# TJMakes_OLED.net
KiCad netlist of a schematic drawn in EasyEDA Pro
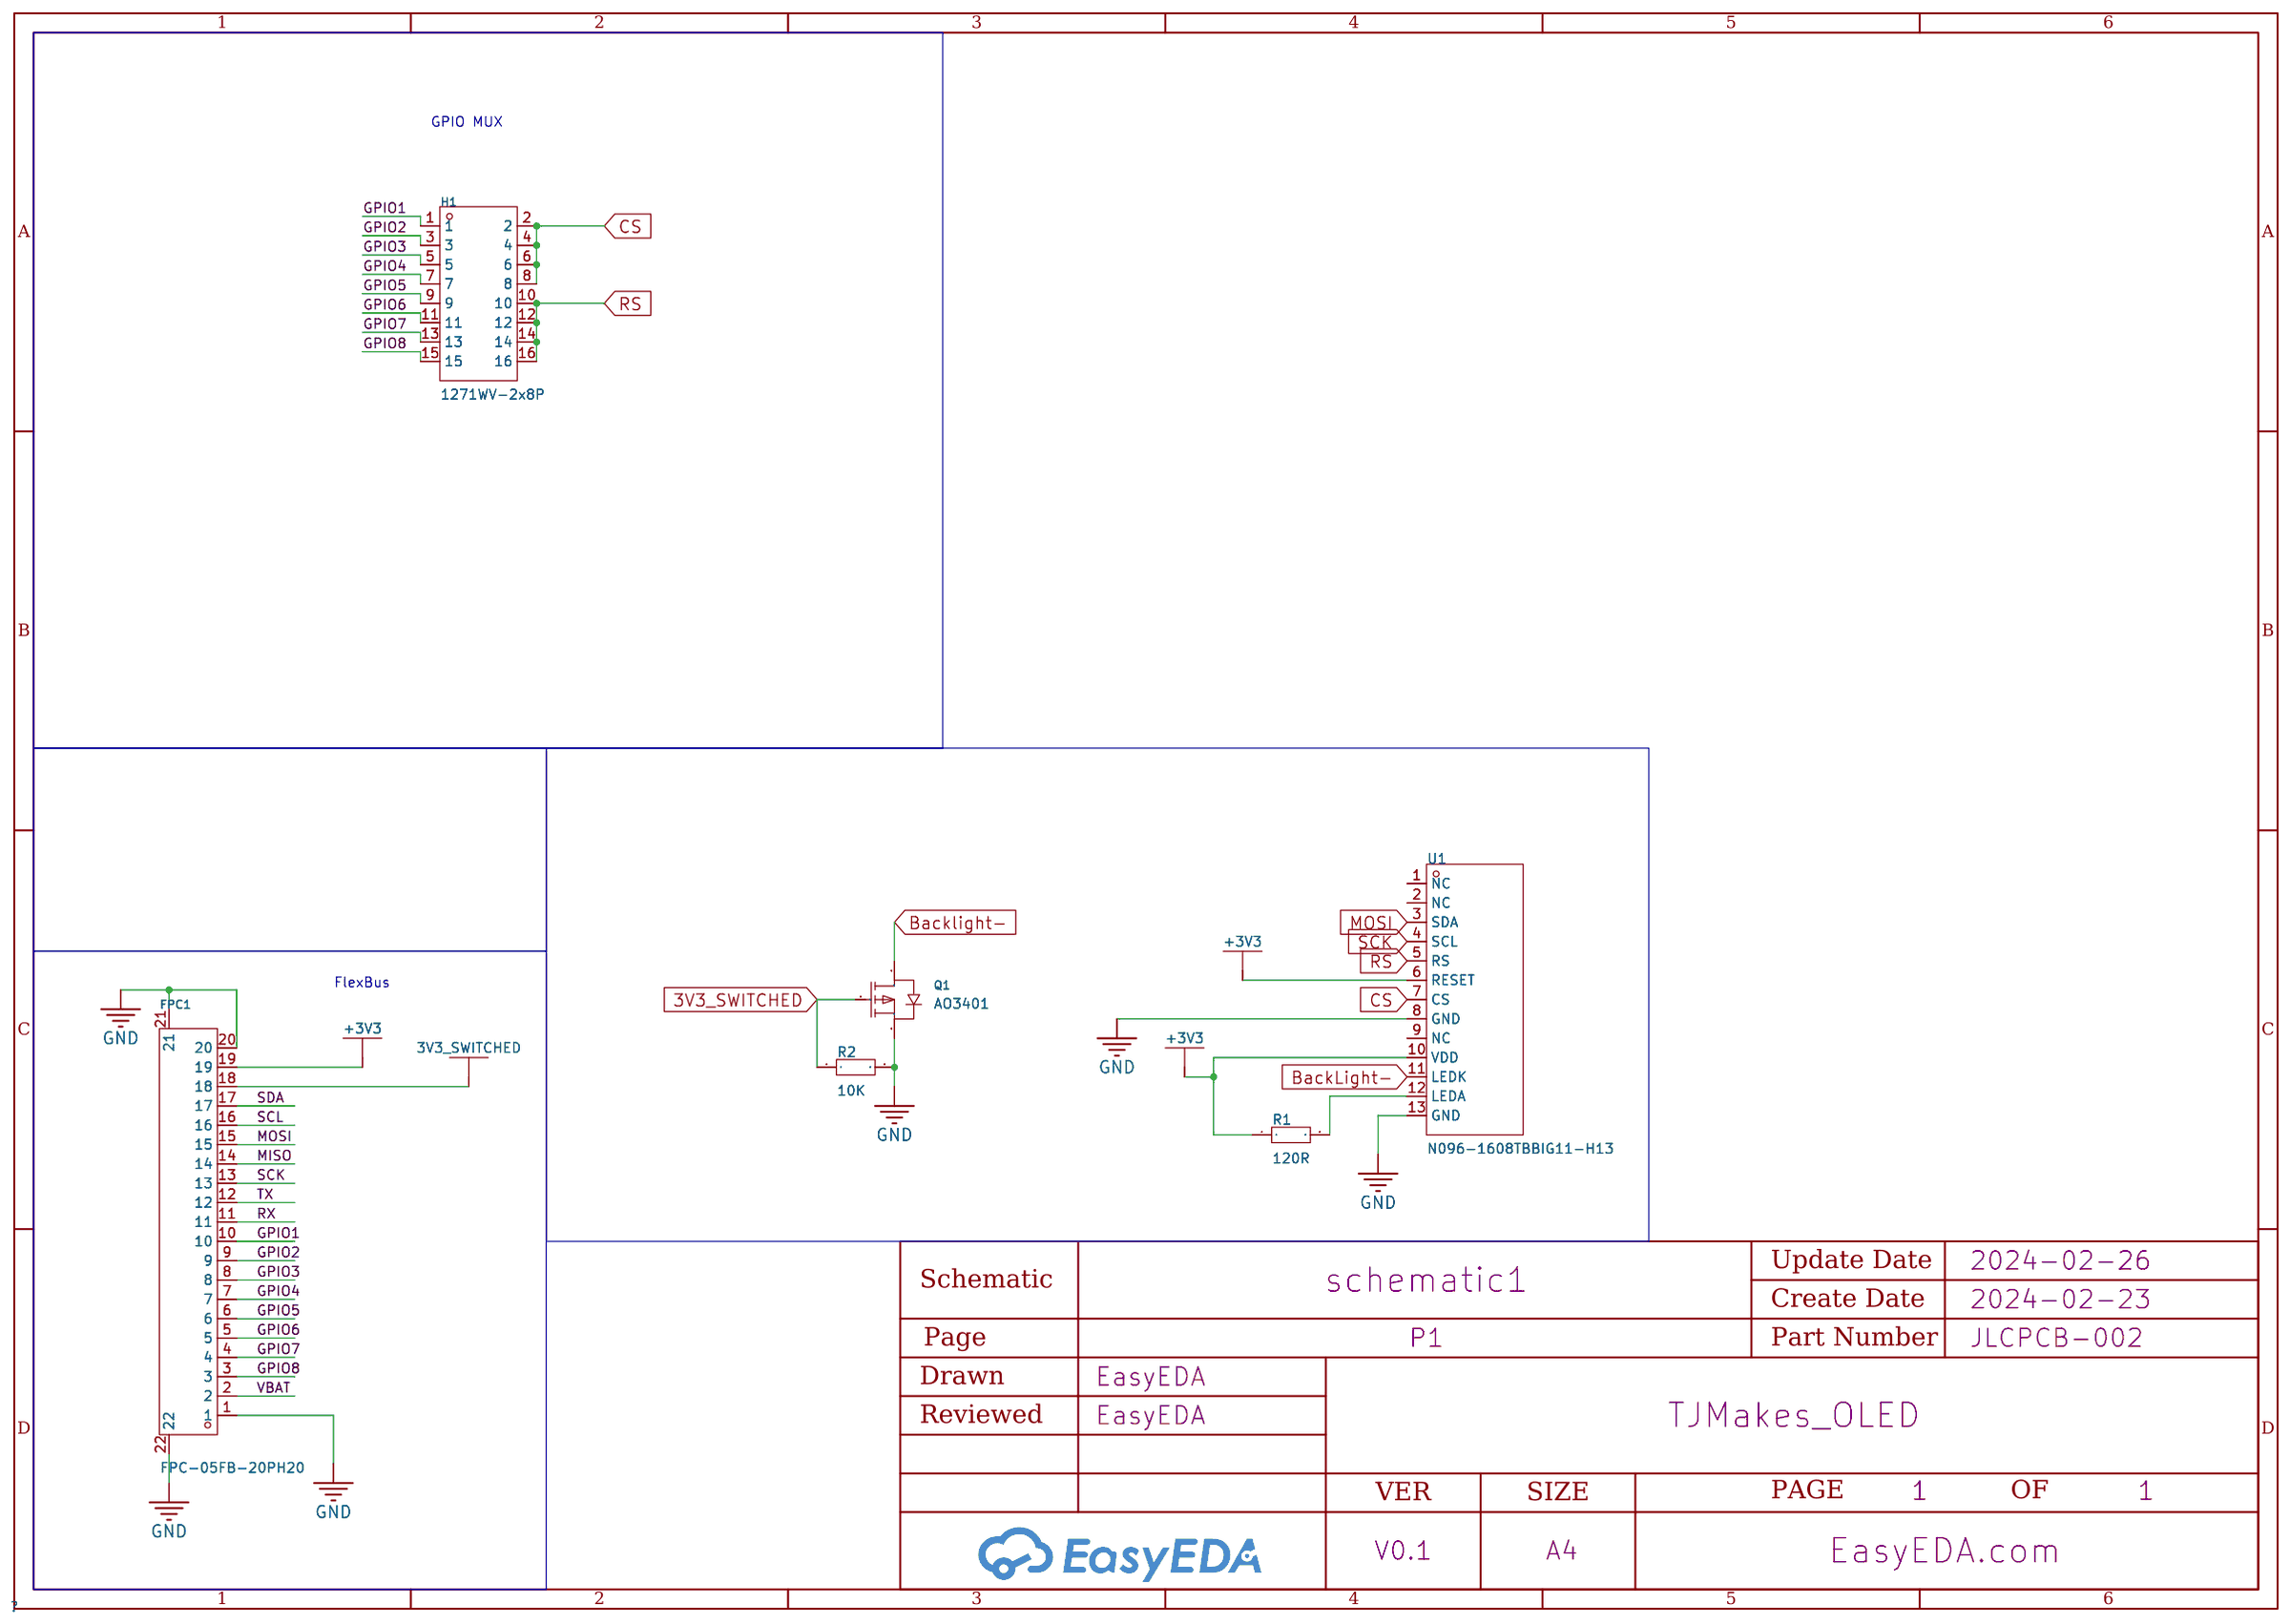
[diagram p0: schematic sheet]

(export (version "E")
  (design (tool "Eeschema 10.0.6"))
  (components
    (comp (ref "FPC1")
      (value "FPC-05FB-20PH20")
      (footprint "easyedapro:FPC-SMD_20P-P0.50_FPC-05FB-20PH20")
      (fields (field (name "Manufacturer") "XUNPU(讯普)"))
      (libsource (lib "easyedapro") (part "FPC-05FB-20PH20"))
    )
    (comp (ref "H1")
      (value "1271WV-2x8P")
      (footprint "easyedapro:HDR-TH_16P-P1.27-V-M-R2-C8-S1.27")
      (fields (field (name "Manufacturer") "kinghelm(金航标)"))
      (libsource (lib "easyedapro") (part "KH-1.27PH180-2X8P-L7.2"))
    )
    (comp (ref "Q1")
      (value "AO3401")
      (footprint "easyedapro:SOT-23-3_L2.9-W1.4-P1.90-LS2.6-BR")
      (fields (field (name "Manufacturer") "TWGMC(台湾迪嘉)"))
      (libsource (lib "easyedapro") (part "AO3401_C727156"))
    )
    (comp (ref "R1")
      (value "120R")
      (footprint "easyedapro:R0603")
      (libsource (lib "easyedapro") (part "Res"))
    )
    (comp (ref "R2") (value "10K") (footprint "easyedapro:R0603") (libsource (lib "easyedapro") (part "Res")))
    (comp (ref "U1")
      (value "N096-1608TBBIG11-H13")
      (footprint "easyedapro:OLED-SMD_ST7735S")
      (description "Main Control Chip:ST7735S Size:0.96")
      (fields (field (name "Manufacturer") "Newvision(新智景)"))
      (libsource (lib "easyedapro") (part "N096-1608TBBIG11-H13"))
    )
  )
  (nets
    (net (code "1") (name "+3V3") (class "Default")
      (node (ref "FPC1") (pin "19") (pinfunction "19_19") (pintype "input"))
      (node (ref "R1") (pin "1") (pinfunction "1_1") (pintype "input"))
      (node (ref "U1") (pin "10") (pinfunction "VDD_10") (pintype "unspecified"))
      (node (ref "U1") (pin "6") (pinfunction "RESET_6") (pintype "unspecified"))
    )
    (net (code "2") (name "/GPIO1") (class "Default")
      (node (ref "FPC1") (pin "10") (pinfunction "10_10") (pintype "input"))
      (node (ref "H1") (pin "1") (pinfunction "1_1") (pintype "input"))
    )
    (net (code "3") (name "/GPIO2") (class "Default")
      (node (ref "FPC1") (pin "9") (pinfunction "9_9") (pintype "input"))
      (node (ref "H1") (pin "3") (pinfunction "3_3") (pintype "input"))
    )
    (net (code "4") (name "/GPIO3") (class "Default")
      (node (ref "FPC1") (pin "8") (pinfunction "8_8") (pintype "input"))
      (node (ref "H1") (pin "5") (pinfunction "5_5") (pintype "input"))
    )
    (net (code "5") (name "/GPIO4") (class "Default")
      (node (ref "FPC1") (pin "7") (pinfunction "7_7") (pintype "input"))
      (node (ref "H1") (pin "7") (pinfunction "7_7") (pintype "input"))
    )
    (net (code "6") (name "/GPIO5") (class "Default")
      (node (ref "FPC1") (pin "6") (pinfunction "6_6") (pintype "input"))
      (node (ref "H1") (pin "9") (pinfunction "9_9") (pintype "input"))
    )
    (net (code "7") (name "/GPIO6") (class "Default")
      (node (ref "FPC1") (pin "5") (pinfunction "5_5") (pintype "input"))
      (node (ref "H1") (pin "11") (pinfunction "11_11") (pintype "input"))
    )
    (net (code "8") (name "/GPIO7") (class "Default")
      (node (ref "FPC1") (pin "4") (pinfunction "4_4") (pintype "input"))
      (node (ref "H1") (pin "13") (pinfunction "13_13") (pintype "input"))
    )
    (net (code "9") (name "/GPIO8") (class "Default")
      (node (ref "FPC1") (pin "3") (pinfunction "3_3") (pintype "input"))
      (node (ref "H1") (pin "15") (pinfunction "15_15") (pintype "input"))
    )
    (net (code "10") (name "/MISO") (class "Default")
      (node (ref "FPC1") (pin "14") (pinfunction "14_14") (pintype "input"))
    )
    (net (code "11") (name "/RX") (class "Default")
      (node (ref "FPC1") (pin "11") (pinfunction "11_11") (pintype "input"))
    )
    (net (code "12") (name "/SCL") (class "Default")
      (node (ref "FPC1") (pin "16") (pinfunction "16_16") (pintype "input"))
    )
    (net (code "13") (name "/SDA") (class "Default")
      (node (ref "FPC1") (pin "17") (pinfunction "17_17") (pintype "input"))
    )
    (net (code "14") (name "/TX") (class "Default")
      (node (ref "FPC1") (pin "12") (pinfunction "12_12") (pintype "input"))
    )
    (net (code "15") (name "/VBAT") (class "Default")
      (node (ref "FPC1") (pin "2") (pinfunction "2_2") (pintype "input"))
    )
    (net (code "16") (name "3V3_SWITCHED") (class "Default")
      (node (ref "FPC1") (pin "18") (pinfunction "18_18") (pintype "input"))
      (node (ref "Q1") (pin "1") (pinfunction "G_1") (pintype "input"))
      (node (ref "R2") (pin "1") (pinfunction "1_1") (pintype "input"))
    )
    (net (code "17") (name "BackLight-") (class "Default")
      (node (ref "U1") (pin "11") (pinfunction "LEDK_11") (pintype "unspecified"))
    )
    (net (code "18") (name "Backlight-") (class "Default")
      (node (ref "Q1") (pin "3") (pinfunction "D_3") (pintype "input"))
    )
    (net (code "19") (name "CS") (class "Default")
      (node (ref "H1") (pin "2") (pinfunction "2_2") (pintype "input"))
      (node (ref "H1") (pin "4") (pinfunction "4_4") (pintype "input"))
      (node (ref "H1") (pin "6") (pinfunction "6_6") (pintype "input"))
      (node (ref "H1") (pin "8") (pinfunction "8_8") (pintype "input"))
      (node (ref "U1") (pin "7") (pinfunction "CS_7") (pintype "unspecified"))
    )
    (net (code "20") (name "GND") (class "Default")
      (node (ref "FPC1") (pin "1") (pinfunction "1_1") (pintype "input"))
      (node (ref "FPC1") (pin "20") (pinfunction "20_20") (pintype "input"))
      (node (ref "FPC1") (pin "21") (pinfunction "21_21") (pintype "input"))
      (node (ref "FPC1") (pin "22") (pinfunction "22_22") (pintype "input"))
      (node (ref "Q1") (pin "2") (pinfunction "S_2") (pintype "input"))
      (node (ref "R2") (pin "2") (pinfunction "2_2") (pintype "input"))
      (node (ref "U1") (pin "13") (pinfunction "GND_13") (pintype "unspecified"))
      (node (ref "U1") (pin "8") (pinfunction "GND_8") (pintype "unspecified"))
    )
    (net (code "21") (name "MOSI") (class "Default")
      (node (ref "FPC1") (pin "15") (pinfunction "15_15") (pintype "input"))
      (node (ref "U1") (pin "3") (pinfunction "SDA_3") (pintype "unspecified"))
    )
    (net (code "22") (name "Net-(U1-LEDA)") (class "Default")
      (node (ref "R1") (pin "2") (pinfunction "2_2") (pintype "input"))
      (node (ref "U1") (pin "12") (pinfunction "LEDA_12") (pintype "unspecified"))
    )
    (net (code "23") (name "RS") (class "Default")
      (node (ref "H1") (pin "10") (pinfunction "10_10") (pintype "input"))
      (node (ref "H1") (pin "12") (pinfunction "12_12") (pintype "input"))
      (node (ref "H1") (pin "14") (pinfunction "14_14") (pintype "input"))
      (node (ref "H1") (pin "16") (pinfunction "16_16") (pintype "input"))
      (node (ref "U1") (pin "5") (pinfunction "RS_5") (pintype "unspecified"))
    )
    (net (code "24") (name "SCK") (class "Default")
      (node (ref "FPC1") (pin "13") (pinfunction "13_13") (pintype "input"))
      (node (ref "U1") (pin "4") (pinfunction "SCL_4") (pintype "unspecified"))
    )
    (net (code "25") (name "unconnected-(U1-NC-Pad1)") (class "Default")
      (node (ref "U1") (pin "1") (pinfunction "NC_1") (pintype "unspecified"))
    )
    (net (code "26") (name "unconnected-(U1-NC-Pad2)") (class "Default")
      (node (ref "U1") (pin "2") (pinfunction "NC_2") (pintype "unspecified"))
    )
    (net (code "27") (name "unconnected-(U1-NC-Pad9)") (class "Default")
      (node (ref "U1") (pin "9") (pinfunction "NC_9") (pintype "unspecified"))
    )
  )
)
